# Sheet2.net
KiCad netlist of a schematic drawn in Altium Designer
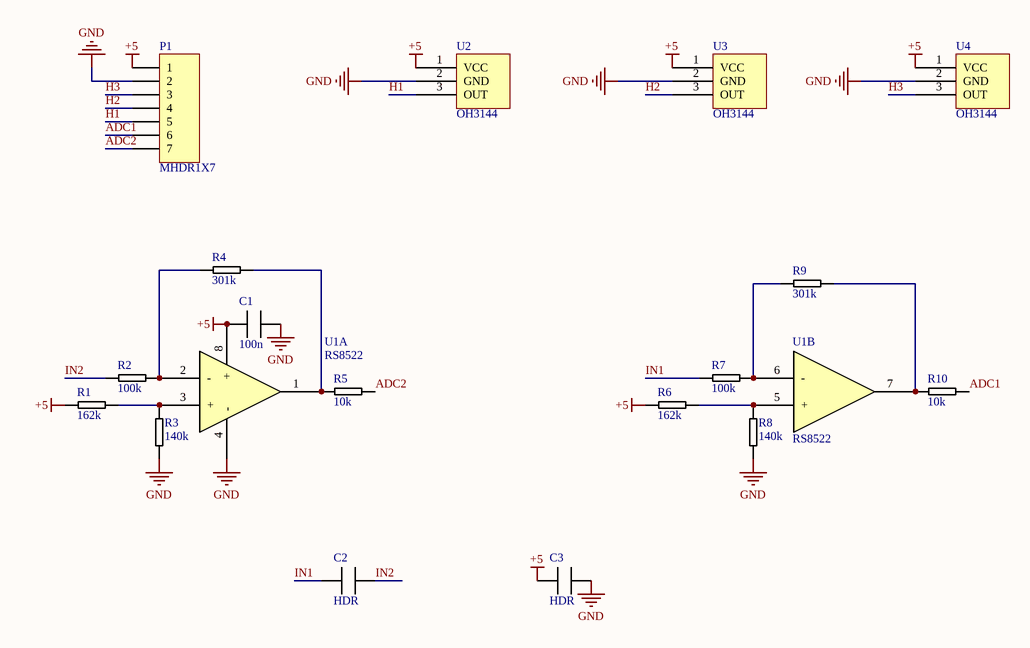
[diagram p0: Sheet2.SchDoc]

(export (version "E")
  (design (tool "Eeschema 10.0.6"))
  (components
    (comp (ref "C1") (value "100n") (footprint "0603") (libsource (lib "LibCfrpg") (part "Cap")))
    (comp (ref "C2") (value "HDR") (footprint "0805") (libsource (lib "LibCfrpg") (part "Cap")))
    (comp (ref "C3") (value "HDR") (footprint "0805") (libsource (lib "LibCfrpg") (part "Cap")))
    (comp (ref "P1")
      (value "MHDR1X7")
      (footprint "MHDR1X7")
      (description "Header, 7-Pin")
      (fields (field (name "PUBLISHER") "Altium Limited"))
      (libsource (lib "Miscellaneous Connectors") (part "MHDR1X7"))
    )
    (comp (ref "R1") (value "162k") (footprint "0603") (libsource (lib "LibCfrpg") (part "Res")))
    (comp (ref "R2") (value "100k") (footprint "0603") (libsource (lib "LibCfrpg") (part "Res")))
    (comp (ref "R3") (value "140k") (footprint "0603") (libsource (lib "LibCfrpg") (part "Res")))
    (comp (ref "R4") (value "301k") (footprint "0603") (libsource (lib "LibCfrpg") (part "Res")))
    (comp (ref "R5") (value "10k") (footprint "0603") (libsource (lib "LibCfrpg") (part "Res")))
    (comp (ref "R6") (value "162k") (footprint "0603") (libsource (lib "LibCfrpg") (part "Res")))
    (comp (ref "R7") (value "100k") (footprint "0603") (libsource (lib "LibCfrpg") (part "Res")))
    (comp (ref "R8") (value "140k") (footprint "0603") (libsource (lib "LibCfrpg") (part "Res")))
    (comp (ref "R9") (value "301k") (footprint "0603") (libsource (lib "LibCfrpg") (part "Res")))
    (comp (ref "R10") (value "10k") (footprint "0603") (libsource (lib "LibCfrpg") (part "Res")))
    (comp (ref "U1") (value "RS8522") (footprint "TDFN-2x2-8L") (libsource (lib "LibCfrpg") (part "RS8522")))
    (comp (ref "U2") (value "OH3144") (footprint "TO-92S") (libsource (lib "LibCfrpg") (part "OH3144")))
    (comp (ref "U3") (value "OH3144") (footprint "TO-92S") (libsource (lib "LibCfrpg") (part "OH3144")))
    (comp (ref "U4") (value "OH3144") (footprint "TO-92S") (libsource (lib "LibCfrpg") (part "OH3144")))
  )
  (nets
    (net (code "1") (name "+5") (class "Default")
      (node (ref "C1") (pin "1") (pintype "passive"))
      (node (ref "C3") (pin "1") (pintype "passive"))
      (node (ref "P1") (pin "1") (pinfunction "1_1") (pintype "passive"))
      (node (ref "R1") (pin "1") (pintype "passive"))
      (node (ref "R6") (pin "1") (pintype "passive"))
      (node (ref "U1") (pin "8") (pinfunction "+_8") (pintype "passive"))
      (node (ref "U2") (pin "1") (pinfunction "VCC_1") (pintype "passive"))
      (node (ref "U3") (pin "1") (pinfunction "VCC_1") (pintype "passive"))
      (node (ref "U4") (pin "1") (pinfunction "VCC_1") (pintype "passive"))
    )
    (net (code "2") (name "/ADC1") (class "Default")
      (node (ref "P1") (pin "6") (pinfunction "6_6") (pintype "passive"))
      (node (ref "R10") (pin "2") (pintype "passive"))
    )
    (net (code "3") (name "/ADC2") (class "Default")
      (node (ref "P1") (pin "7") (pinfunction "7_7") (pintype "passive"))
      (node (ref "R5") (pin "2") (pintype "passive"))
    )
    (net (code "4") (name "/H1") (class "Default")
      (node (ref "P1") (pin "5") (pinfunction "5_5") (pintype "passive"))
      (node (ref "U2") (pin "3") (pinfunction "OUT_3") (pintype "passive"))
    )
    (net (code "5") (name "/H2") (class "Default")
      (node (ref "P1") (pin "4") (pinfunction "4_4") (pintype "passive"))
      (node (ref "U3") (pin "3") (pinfunction "OUT_3") (pintype "passive"))
    )
    (net (code "6") (name "/H3") (class "Default")
      (node (ref "P1") (pin "3") (pinfunction "3_3") (pintype "passive"))
      (node (ref "U4") (pin "3") (pinfunction "OUT_3") (pintype "passive"))
    )
    (net (code "7") (name "/IN1") (class "Default")
      (node (ref "C2") (pin "1") (pintype "passive"))
      (node (ref "R7") (pin "1") (pintype "passive"))
    )
    (net (code "8") (name "/IN2") (class "Default")
      (node (ref "C2") (pin "2") (pintype "passive"))
      (node (ref "R2") (pin "1") (pintype "passive"))
    )
    (net (code "9") (name "GND") (class "Default")
      (node (ref "C1") (pin "2") (pintype "passive"))
      (node (ref "C3") (pin "2") (pintype "passive"))
      (node (ref "P1") (pin "2") (pinfunction "2_2") (pintype "passive"))
      (node (ref "R3") (pin "1") (pintype "passive"))
      (node (ref "R8") (pin "1") (pintype "passive"))
      (node (ref "U1") (pin "4") (pinfunction "-_4") (pintype "passive"))
      (node (ref "U2") (pin "2") (pinfunction "GND_2") (pintype "passive"))
      (node (ref "U3") (pin "2") (pinfunction "GND_2") (pintype "passive"))
      (node (ref "U4") (pin "2") (pinfunction "GND_2") (pintype "passive"))
    )
    (net (code "10") (name "Net-(R1-Pad2)") (class "Default")
      (node (ref "R1") (pin "2") (pintype "passive"))
      (node (ref "R3") (pin "2") (pintype "passive"))
      (node (ref "U1") (pin "3") (pinfunction "+_3") (pintype "passive"))
    )
    (net (code "11") (name "Net-(R2-Pad2)") (class "Default")
      (node (ref "R2") (pin "2") (pintype "passive"))
      (node (ref "R4") (pin "1") (pintype "passive"))
      (node (ref "U1") (pin "2") (pinfunction "-_2") (pintype "passive"))
    )
    (net (code "12") (name "Net-(R4-Pad2)") (class "Default")
      (node (ref "R4") (pin "2") (pintype "passive"))
      (node (ref "R5") (pin "1") (pintype "passive"))
      (node (ref "U1") (pin "1") (pintype "passive"))
    )
    (net (code "13") (name "Net-(R10-Pad1)") (class "Default")
      (node (ref "R10") (pin "1") (pintype "passive"))
      (node (ref "R9") (pin "2") (pintype "passive"))
      (node (ref "U1") (pin "7") (pintype "passive"))
    )
    (net (code "14") (name "Net-(U1B-+)") (class "Default")
      (node (ref "R6") (pin "2") (pintype "passive"))
      (node (ref "R8") (pin "2") (pintype "passive"))
      (node (ref "U1") (pin "5") (pinfunction "+_5") (pintype "passive"))
    )
    (net (code "15") (name "Net-(U1B--)") (class "Default")
      (node (ref "R7") (pin "2") (pintype "passive"))
      (node (ref "R9") (pin "1") (pintype "passive"))
      (node (ref "U1") (pin "6") (pinfunction "-_6") (pintype "passive"))
    )
  )
)
